# S7CAS-PLEIADES-CARTE-MERE_Pxx_FPGA_bank2.net
KiCad netlist of a schematic drawn in Altium Designer
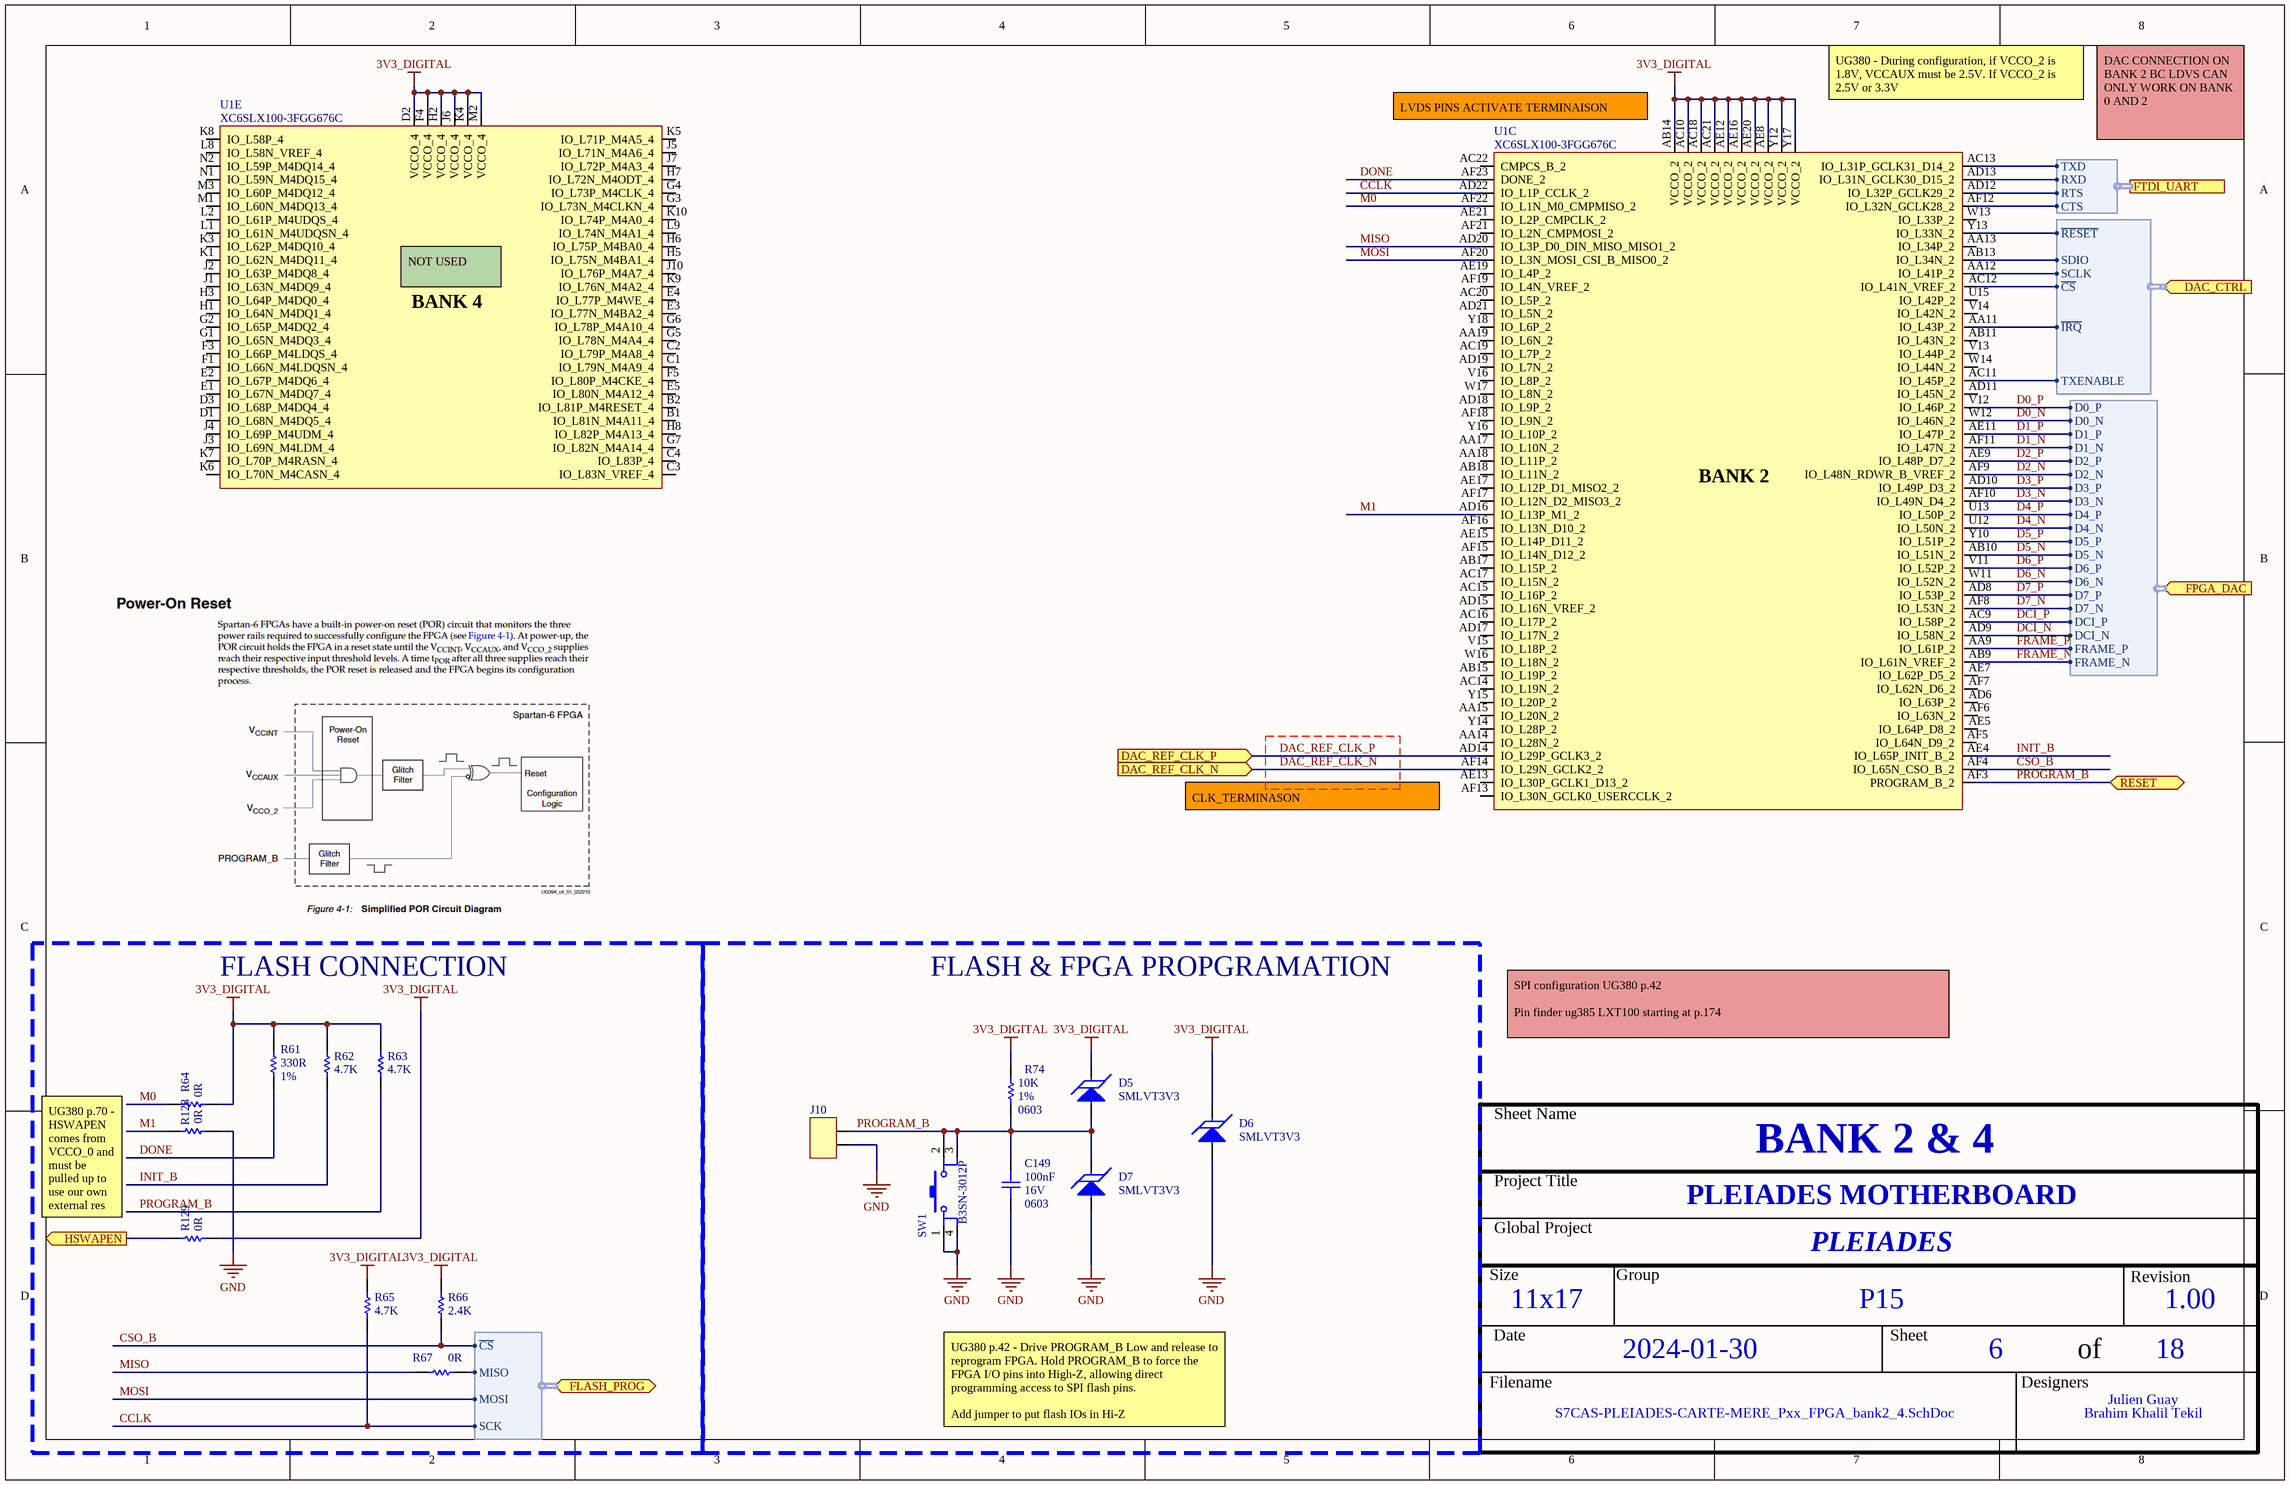
[diagram p0: S7CAS-PLEIADES-CARTE-MERE_Pxx_FPGA_bank2_4.SchDoc]

(export (version "E")
  (design (tool "Eeschema 10.0.6"))
  (components
    (comp (ref "C149")
      (value "100nF")
      (footprint "CAP_0603")
      (description "CAP - 0603")
      (fields
        (field (name "VOLTAGE") "16V")
        (field (name "PACKAGE") "0603")
        (field (name "CREATEDBY") "Jonathan Bouchard")
      )
      (libsource (lib "S7CAS_LIB2023") (part "CAP - 0603"))
    )
    (comp (ref "D5")
      (value "SMLVT3V3")
      (footprint "TVS_POW_SMLVT3V3")
      (description "TVS - 3.3V 10.3V 600W - DO214AA")
      (fields
        (field (name "CREATEDBY/DATE") "Jonathan Bouchard - 2019-04-27")
        (field (name "VERIFIEDBY") "Nicolas V. (2019-05-06)")
      )
      (libsource (lib "S7CAS_LIB2023") (part "TVS_POW_SMLVT3V3"))
    )
    (comp (ref "D6")
      (value "SMLVT3V3")
      (footprint "TVS_POW_SMLVT3V3")
      (description "TVS - 3.3V 10.3V 600W - DO214AA")
      (fields
        (field (name "CREATEDBY/DATE") "Jonathan Bouchard - 2019-04-27")
        (field (name "VERIFIEDBY") "Nicolas V. (2019-05-06)")
      )
      (libsource (lib "S7CAS_LIB2023") (part "TVS_POW_SMLVT3V3"))
    )
    (comp (ref "D7")
      (value "SMLVT3V3")
      (footprint "TVS_POW_SMLVT3V3")
      (description "TVS - 3.3V 10.3V 600W - DO214AA")
      (fields
        (field (name "CREATEDBY/DATE") "Jonathan Bouchard - 2019-04-27")
        (field (name "VERIFIEDBY") "Nicolas V. (2019-05-06)")
      )
      (libsource (lib "S7CAS_LIB2023") (part "TVS_POW_SMLVT3V3"))
    )
    (comp (ref "J10")
      (value "Part Number")
      (footprint "MALE HEADER - 1x2 2.54mm")
      (description "MALE HEADER - 2.54mm 1x2")
      (libsource (lib "S7CAS_LIB2023") (part "MALE HEADER - 1x2 2.54mm"))
    )
    (comp (ref "R61")
      (value "330R")
      (footprint "RES_0603")
      (description "RES - 0603")
      (fields (field (name "PRECISION") "1%") (field (name "CREATEDBY") "Jonathan Bouchard"))
      (libsource (lib "S7CAS_LIB2023") (part "RES - 0603"))
    )
    (comp (ref "R62")
      (value "4.7K")
      (footprint "RES_0603")
      (description "RES - 0603")
      (fields (field (name "CREATEDBY") "Jonathan Bouchard"))
      (libsource (lib "S7CAS_LIB2023") (part "RES - 0603"))
    )
    (comp (ref "R63")
      (value "4.7K")
      (footprint "RES_0603")
      (description "RES - 0603")
      (fields (field (name "CREATEDBY") "Jonathan Bouchard"))
      (libsource (lib "S7CAS_LIB2023") (part "RES - 0603"))
    )
    (comp (ref "R64")
      (value "0R")
      (footprint "RES_0603")
      (description "RES - 0603")
      (fields (field (name "CREATEDBY") "Jonathan Bouchard"))
      (libsource (lib "S7CAS_LIB2023") (part "RES - 0603"))
    )
    (comp (ref "R65")
      (value "4.7K")
      (footprint "RES_0603")
      (description "RES - 0603")
      (fields (field (name "CREATEDBY") "Jonathan Bouchard"))
      (libsource (lib "S7CAS_LIB2023") (part "RES - 0603"))
    )
    (comp (ref "R66")
      (value "2.4K")
      (footprint "RES_0603")
      (description "RES - 0603")
      (fields (field (name "CREATEDBY") "Jonathan Bouchard"))
      (libsource (lib "S7CAS_LIB2023") (part "RES - 0603"))
    )
    (comp (ref "R67")
      (value "0R")
      (footprint "RES_0603")
      (description "RES - 0603")
      (fields (field (name "CREATEDBY") "Jonathan Bouchard"))
      (libsource (lib "S7CAS_LIB2023") (part "RES - 0603"))
    )
    (comp (ref "R74")
      (value "10K")
      (footprint "RES_0603")
      (description "RES - 0603")
      (fields
        (field (name "PACKAGE") "0603")
        (field (name "PRECISION") "1%")
        (field (name "CREATEDBY") "Jonathan Bouchard")
      )
      (libsource (lib "S7CAS_LIB2023") (part "RES - 0603"))
    )
    (comp (ref "R128")
      (value "0R")
      (footprint "RES_0603")
      (description "RES - 0603")
      (fields (field (name "CREATEDBY") "Jonathan Bouchard"))
      (libsource (lib "S7CAS_LIB2023") (part "RES - 0603"))
    )
    (comp (ref "R129")
      (value "0R")
      (footprint "RES_0603")
      (description "RES - 0603")
      (fields (field (name "CREATEDBY") "Jonathan Bouchard"))
      (libsource (lib "S7CAS_LIB2023") (part "RES - 0603"))
    )
    (comp (ref "SW1")
      (value "B3SN-3012P")
      (footprint "SWI_TACT_B3SN-3012P")
      (description "SWI - TACT SPST-NO 0.05A 24V - 4-SMD")
      (fields
        (field (name "MFG") "Omron")
        (field (name "VOLTAGE") "24V")
        (field (name "CREATEDBY") "Jonathan Bouchard")
      )
      (libsource (lib "S7CAS_LIB2023") (part "SWI_TACT_B3SN-3012P"))
    )
    (comp (ref "U1")
      (value "XC6SLX100-3FGG676C")
      (footprint "FPGA_XILINX_FGG676")
      (description "FPGA - XILINX SPARTAN 6 480 I/O - BGA-676")
      (fields
        (field (name "VOLTAGE") "1.14 V ~ 1.26 V")
        (field (name "MFG") "Xilinx")
        (field (name "CREATEDBY") "Jonathan Bouchard")
      )
      (libsource (lib "S7CAS_LIB2023") (part "FPGA_XC6SLX100-3FGG676C"))
    )
  )
  (nets
    (net (code "5") (name "/CCLK") (class "Default")
      (node (ref "R65") (pin "1") (pinfunction "1_1") (pintype "passive"))
      (node (ref "U1") (pin "AD22") (pinfunction "IO_L1P_CCLK_2_AD22") (pintype "passive"))
    )
    (net (code "6") (name "/CSO_B") (class "Default")
      (node (ref "R66") (pin "1") (pinfunction "1_1") (pintype "passive"))
      (node (ref "U1") (pin "AF4") (pinfunction "IO_L65N_CSO_B_2_AF4") (pintype "passive"))
    )
    (net (code "7") (name "/CTS") (class "Default")
      (node (ref "U1") (pin "AF12") (pinfunction "IO_L32N_GCLK28_2_AF12") (pintype "passive"))
    )
    (net (code "8") (name "/D0_N") (class "Default")
      (node (ref "U1") (pin "W12") (pinfunction "IO_L46N_2_W12") (pintype "passive"))
    )
    (net (code "9") (name "/D0_P") (class "Default")
      (node (ref "U1") (pin "V12") (pinfunction "IO_L46P_2_V12") (pintype "passive"))
    )
    (net (code "10") (name "/D1_N") (class "Default")
      (node (ref "U1") (pin "AF11") (pinfunction "IO_L47N_2_AF11") (pintype "passive"))
    )
    (net (code "11") (name "/D1_P") (class "Default")
      (node (ref "U1") (pin "AE11") (pinfunction "IO_L47P_2_AE11") (pintype "passive"))
    )
    (net (code "12") (name "/D2_N") (class "Default")
      (node (ref "U1") (pin "AF9") (pinfunction "IO_L48N_RDWR_B_VREF_2_AF9") (pintype "passive"))
    )
    (net (code "13") (name "/D2_P") (class "Default")
      (node (ref "U1") (pin "AE9") (pinfunction "IO_L48P_D7_2_AE9") (pintype "passive"))
    )
    (net (code "14") (name "/D3_N") (class "Default")
      (node (ref "U1") (pin "AF10") (pinfunction "IO_L49N_D4_2_AF10") (pintype "passive"))
    )
    (net (code "15") (name "/D3_P") (class "Default")
      (node (ref "U1") (pin "AD10") (pinfunction "IO_L49P_D3_2_AD10") (pintype "passive"))
    )
    (net (code "16") (name "/D4_N") (class "Default")
      (node (ref "U1") (pin "U12") (pinfunction "IO_L50N_2_U12") (pintype "passive"))
    )
    (net (code "17") (name "/D4_P") (class "Default")
      (node (ref "U1") (pin "U13") (pinfunction "IO_L50P_2_U13") (pintype "passive"))
    )
    (net (code "18") (name "/D5_N") (class "Default")
      (node (ref "U1") (pin "AB10") (pinfunction "IO_L51N_2_AB10") (pintype "passive"))
    )
    (net (code "19") (name "/D5_P") (class "Default")
      (node (ref "U1") (pin "Y10") (pinfunction "IO_L51P_2_Y10") (pintype "passive"))
    )
    (net (code "20") (name "/D6_N") (class "Default")
      (node (ref "U1") (pin "W11") (pinfunction "IO_L52N_2_W11") (pintype "passive"))
    )
    (net (code "21") (name "/D6_P") (class "Default")
      (node (ref "U1") (pin "V11") (pinfunction "IO_L52P_2_V11") (pintype "passive"))
    )
    (net (code "22") (name "/D7_N") (class "Default")
      (node (ref "U1") (pin "AF8") (pinfunction "IO_L53N_2_AF8") (pintype "passive"))
    )
    (net (code "23") (name "/D7_P") (class "Default")
      (node (ref "U1") (pin "AD8") (pinfunction "IO_L53P_2_AD8") (pintype "passive"))
    )
    (net (code "25") (name "/DAC_REF_CLK_N") (class "Default")
      (node (ref "U1") (pin "AF14") (pinfunction "IO_L29N_GCLK2_2_AF14") (pintype "passive"))
    )
    (net (code "26") (name "/DAC_REF_CLK_P") (class "Default")
      (node (ref "U1") (pin "AD14") (pinfunction "IO_L29P_GCLK3_2_AD14") (pintype "passive"))
    )
    (net (code "27") (name "/DCI_N") (class "Default")
      (node (ref "U1") (pin "AD9") (pinfunction "IO_L58N_2_AD9") (pintype "passive"))
    )
    (net (code "28") (name "/DCI_P") (class "Default")
      (node (ref "U1") (pin "AC9") (pinfunction "IO_L58P_2_AC9") (pintype "passive"))
    )
    (net (code "29") (name "/DONE") (class "Default")
      (node (ref "R61") (pin "1") (pinfunction "1_1") (pintype "passive"))
      (node (ref "U1") (pin "AF23") (pinfunction "DONE_2_AF23") (pintype "passive"))
    )
    (net (code "30") (name "/FRAME_N") (class "Default")
      (node (ref "U1") (pin "AB9") (pinfunction "IO_L61N_VREF_2_AB9") (pintype "passive"))
    )
    (net (code "31") (name "/FRAME_P") (class "Default")
      (node (ref "U1") (pin "AA9") (pinfunction "IO_L61P_2_AA9") (pintype "passive"))
    )
    (net (code "32") (name "/HSWAPEN") (class "Default")
      (node (ref "R129") (pin "1") (pinfunction "1_1") (pintype "passive"))
    )
    (net (code "33") (name "/INIT_B") (class "Default")
      (node (ref "R62") (pin "1") (pinfunction "1_1") (pintype "passive"))
      (node (ref "U1") (pin "AE4") (pinfunction "IO_L65P_INIT_B_2_AE4") (pintype "passive"))
    )
    (net (code "34") (name "/M0") (class "Default")
      (node (ref "R64") (pin "1") (pinfunction "1_1") (pintype "passive"))
      (node (ref "U1") (pin "AF22") (pinfunction "IO_L1N_M0_CMPMISO_2_AF22") (pintype "passive"))
    )
    (net (code "35") (name "/M1") (class "Default")
      (node (ref "R128") (pin "1") (pinfunction "1_1") (pintype "passive"))
      (node (ref "U1") (pin "AD16") (pinfunction "IO_L13P_M1_2_AD16") (pintype "passive"))
    )
    (net (code "36") (name "/MISO") (class "Default")
      (node (ref "R67") (pin "2") (pinfunction "2_2") (pintype "passive"))
      (node (ref "U1") (pin "AD20") (pinfunction "IO_L3P_D0_DIN_MISO_MISO1_2_AD20") (pintype "passive"))
    )
    (net (code "37") (name "/MOSI") (class "Default")
      (node (ref "U1") (pin "AF20") (pinfunction "IO_L3N_MOSI_CSI_B_MISO0_2_AF20") (pintype "passive"))
    )
    (net (code "38") (name "/PROGRAM_B") (class "Default")
      (node (ref "C149") (pin "2") (pinfunction "2_2") (pintype "passive"))
      (node (ref "D5") (pin "A") (pinfunction "A_A") (pintype "passive"))
      (node (ref "D7") (pin "K") (pinfunction "K_K") (pintype "passive"))
      (node (ref "J10") (pin "1") (pinfunction "1_1") (pintype "passive"))
      (node (ref "R63") (pin "1") (pinfunction "1_1") (pintype "passive"))
      (node (ref "R74") (pin "1") (pinfunction "1_1") (pintype "passive"))
      (node (ref "SW1") (pin "2") (pinfunction "2_2") (pintype "passive"))
      (node (ref "SW1") (pin "3") (pinfunction "3_3") (pintype "passive"))
      (node (ref "U1") (pin "AF3") (pinfunction "PROGRAM_B_2_AF3") (pintype "passive"))
    )
    (net (code "39") (name "/RTS") (class "Default")
      (node (ref "U1") (pin "AD12") (pinfunction "IO_L32P_GCLK29_2_AD12") (pintype "passive"))
    )
    (net (code "40") (name "/RXD") (class "Default")
      (node (ref "U1") (pin "AD13") (pinfunction "IO_L31N_GCLK30_D15_2_AD13") (pintype "passive"))
    )
    (net (code "41") (name "/SCLK") (class "Default")
      (node (ref "U1") (pin "AA12") (pinfunction "IO_L41P_2_AA12") (pintype "passive"))
    )
    (net (code "42") (name "/SDIO") (class "Default")
      (node (ref "U1") (pin "AB13") (pinfunction "IO_L34N_2_AB13") (pintype "passive"))
    )
    (net (code "43") (name "/TXD") (class "Default")
      (node (ref "U1") (pin "AC13") (pinfunction "IO_L31P_GCLK31_D14_2_AC13") (pintype "passive"))
    )
    (net (code "44") (name "/TXENABLE") (class "Default")
      (node (ref "U1") (pin "AC11") (pinfunction "IO_L45P_2_AC11") (pintype "passive"))
    )
    (net (code "48") (name "/~{IRQ}") (class "Default")
      (node (ref "U1") (pin "AA11") (pinfunction "IO_L43P_2_AA11") (pintype "passive"))
    )
    (net (code "49") (name "/~{RESET}") (class "Default")
      (node (ref "U1") (pin "Y13") (pinfunction "IO_L33N_2_Y13") (pintype "passive"))
    )
    (net (code "50") (name "3V3_DIGITAL") (class "Default")
      (node (ref "D5") (pin "K") (pinfunction "K_K") (pintype "passive"))
      (node (ref "D6") (pin "K") (pinfunction "K_K") (pintype "passive"))
      (node (ref "R129") (pin "2") (pinfunction "2_2") (pintype "passive"))
      (node (ref "R61") (pin "2") (pinfunction "2_2") (pintype "passive"))
      (node (ref "R62") (pin "2") (pinfunction "2_2") (pintype "passive"))
      (node (ref "R63") (pin "2") (pinfunction "2_2") (pintype "passive"))
      (node (ref "R64") (pin "2") (pinfunction "2_2") (pintype "passive"))
      (node (ref "R65") (pin "2") (pinfunction "2_2") (pintype "passive"))
      (node (ref "R66") (pin "2") (pinfunction "2_2") (pintype "passive"))
      (node (ref "R74") (pin "2") (pinfunction "2_2") (pintype "passive"))
      (node (ref "U1") (pin "AB14") (pinfunction "VCCO_2_AB14") (pintype "passive"))
      (node (ref "U1") (pin "AC10") (pinfunction "VCCO_2_AC10") (pintype "passive"))
      (node (ref "U1") (pin "AC18") (pinfunction "VCCO_2_AC18") (pintype "passive"))
      (node (ref "U1") (pin "AC21") (pinfunction "VCCO_2_AC21") (pintype "passive"))
      (node (ref "U1") (pin "AE12") (pinfunction "VCCO_2_AE12") (pintype "passive"))
      (node (ref "U1") (pin "AE16") (pinfunction "VCCO_2_AE16") (pintype "passive"))
      (node (ref "U1") (pin "AE20") (pinfunction "VCCO_2_AE20") (pintype "passive"))
      (node (ref "U1") (pin "AE8") (pinfunction "VCCO_2_AE8") (pintype "passive"))
      (node (ref "U1") (pin "D2") (pinfunction "VCCO_4_D2") (pintype "passive"))
      (node (ref "U1") (pin "F4") (pinfunction "VCCO_4_F4") (pintype "passive"))
      (node (ref "U1") (pin "H2") (pinfunction "VCCO_4_H2") (pintype "passive"))
      (node (ref "U1") (pin "J6") (pinfunction "VCCO_4_J6") (pintype "passive"))
      (node (ref "U1") (pin "K4") (pinfunction "VCCO_4_K4") (pintype "passive"))
      (node (ref "U1") (pin "M2") (pinfunction "VCCO_4_M2") (pintype "passive"))
      (node (ref "U1") (pin "Y12") (pinfunction "VCCO_2_Y12") (pintype "passive"))
      (node (ref "U1") (pin "Y17") (pinfunction "VCCO_2_Y17") (pintype "passive"))
    )
    (net (code "51") (name "GND") (class "Default")
      (node (ref "C149") (pin "1") (pinfunction "1_1") (pintype "passive"))
      (node (ref "D6") (pin "A") (pinfunction "A_A") (pintype "passive"))
      (node (ref "D7") (pin "A") (pinfunction "A_A") (pintype "passive"))
      (node (ref "J10") (pin "2") (pinfunction "2_2") (pintype "passive"))
      (node (ref "R128") (pin "2") (pinfunction "2_2") (pintype "passive"))
      (node (ref "SW1") (pin "1") (pinfunction "1_1") (pintype "passive"))
      (node (ref "SW1") (pin "4") (pinfunction "4_4") (pintype "passive"))
    )
    (net (code "52") (name "unconnected-(R67-Pad1)") (class "Default")
      (node (ref "R67") (pin "1") (pinfunction "1_1") (pintype "passive"))
    )
    (net (code "53") (name "unconnected-(U1C-CMPCS_B_2-PadAC22)") (class "Default")
      (node (ref "U1") (pin "AC22") (pinfunction "CMPCS_B_2_AC22") (pintype "passive"))
    )
    (net (code "54") (name "unconnected-(U1C-IO_L2N_CMPMOSI_2-PadAF21)") (class "Default")
      (node (ref "U1") (pin "AF21") (pinfunction "IO_L2N_CMPMOSI_2_AF21") (pintype "passive"))
    )
    (net (code "55") (name "unconnected-(U1C-IO_L2P_CMPCLK_2-PadAE21)") (class "Default")
      (node (ref "U1") (pin "AE21") (pinfunction "IO_L2P_CMPCLK_2_AE21") (pintype "passive"))
    )
    (net (code "56") (name "unconnected-(U1C-IO_L4N_VREF_2-PadAF19)") (class "Default")
      (node (ref "U1") (pin "AF19") (pinfunction "IO_L4N_VREF_2_AF19") (pintype "passive"))
    )
    (net (code "57") (name "unconnected-(U1C-IO_L4P_2-PadAE19)") (class "Default")
      (node (ref "U1") (pin "AE19") (pinfunction "IO_L4P_2_AE19") (pintype "passive"))
    )
    (net (code "58") (name "unconnected-(U1C-IO_L5N_2-PadAD21)") (class "Default")
      (node (ref "U1") (pin "AD21") (pinfunction "IO_L5N_2_AD21") (pintype "passive"))
    )
    (net (code "59") (name "unconnected-(U1C-IO_L5P_2-PadAC20)") (class "Default")
      (node (ref "U1") (pin "AC20") (pinfunction "IO_L5P_2_AC20") (pintype "passive"))
    )
    (net (code "60") (name "unconnected-(U1C-IO_L6N_2-PadAA19)") (class "Default")
      (node (ref "U1") (pin "AA19") (pinfunction "IO_L6N_2_AA19") (pintype "passive"))
    )
    (net (code "61") (name "unconnected-(U1C-IO_L6P_2-PadY18)") (class "Default")
      (node (ref "U1") (pin "Y18") (pinfunction "IO_L6P_2_Y18") (pintype "passive"))
    )
    (net (code "62") (name "unconnected-(U1C-IO_L7N_2-PadAD19)") (class "Default")
      (node (ref "U1") (pin "AD19") (pinfunction "IO_L7N_2_AD19") (pintype "passive"))
    )
    (net (code "63") (name "unconnected-(U1C-IO_L7P_2-PadAC19)") (class "Default")
      (node (ref "U1") (pin "AC19") (pinfunction "IO_L7P_2_AC19") (pintype "passive"))
    )
    (net (code "64") (name "unconnected-(U1C-IO_L8N_2-PadW17)") (class "Default")
      (node (ref "U1") (pin "W17") (pinfunction "IO_L8N_2_W17") (pintype "passive"))
    )
    (net (code "65") (name "unconnected-(U1C-IO_L8P_2-PadV16)") (class "Default")
      (node (ref "U1") (pin "V16") (pinfunction "IO_L8P_2_V16") (pintype "passive"))
    )
    (net (code "66") (name "unconnected-(U1C-IO_L9N_2-PadAF18)") (class "Default")
      (node (ref "U1") (pin "AF18") (pinfunction "IO_L9N_2_AF18") (pintype "passive"))
    )
    (net (code "67") (name "unconnected-(U1C-IO_L9P_2-PadAD18)") (class "Default")
      (node (ref "U1") (pin "AD18") (pinfunction "IO_L9P_2_AD18") (pintype "passive"))
    )
    (net (code "68") (name "unconnected-(U1C-IO_L10N_2-PadAA17)") (class "Default")
      (node (ref "U1") (pin "AA17") (pinfunction "IO_L10N_2_AA17") (pintype "passive"))
    )
    (net (code "69") (name "unconnected-(U1C-IO_L10P_2-PadY16)") (class "Default")
      (node (ref "U1") (pin "Y16") (pinfunction "IO_L10P_2_Y16") (pintype "passive"))
    )
    (net (code "70") (name "unconnected-(U1C-IO_L11N_2-PadAB18)") (class "Default")
      (node (ref "U1") (pin "AB18") (pinfunction "IO_L11N_2_AB18") (pintype "passive"))
    )
    (net (code "71") (name "unconnected-(U1C-IO_L11P_2-PadAA18)") (class "Default")
      (node (ref "U1") (pin "AA18") (pinfunction "IO_L11P_2_AA18") (pintype "passive"))
    )
    (net (code "72") (name "unconnected-(U1C-IO_L12N_D2_MISO3_2-PadAF17)") (class "Default")
      (node (ref "U1") (pin "AF17") (pinfunction "IO_L12N_D2_MISO3_2_AF17") (pintype "passive"))
    )
    (net (code "73") (name "unconnected-(U1C-IO_L12P_D1_MISO2_2-PadAE17)") (class "Default")
      (node (ref "U1") (pin "AE17") (pinfunction "IO_L12P_D1_MISO2_2_AE17") (pintype "passive"))
    )
    (net (code "74") (name "unconnected-(U1C-IO_L13N_D10_2-PadAF16)") (class "Default")
      (node (ref "U1") (pin "AF16") (pinfunction "IO_L13N_D10_2_AF16") (pintype "passive"))
    )
    (net (code "75") (name "unconnected-(U1C-IO_L14N_D12_2-PadAF15)") (class "Default")
      (node (ref "U1") (pin "AF15") (pinfunction "IO_L14N_D12_2_AF15") (pintype "passive"))
    )
    (net (code "76") (name "unconnected-(U1C-IO_L14P_D11_2-PadAE15)") (class "Default")
      (node (ref "U1") (pin "AE15") (pinfunction "IO_L14P_D11_2_AE15") (pintype "passive"))
    )
    (net (code "77") (name "unconnected-(U1C-IO_L15N_2-PadAC17)") (class "Default")
      (node (ref "U1") (pin "AC17") (pinfunction "IO_L15N_2_AC17") (pintype "passive"))
    )
    (net (code "78") (name "unconnected-(U1C-IO_L15P_2-PadAB17)") (class "Default")
      (node (ref "U1") (pin "AB17") (pinfunction "IO_L15P_2_AB17") (pintype "passive"))
    )
    (net (code "79") (name "unconnected-(U1C-IO_L16N_VREF_2-PadAD15)") (class "Default")
      (node (ref "U1") (pin "AD15") (pinfunction "IO_L16N_VREF_2_AD15") (pintype "passive"))
    )
    (net (code "80") (name "unconnected-(U1C-IO_L16P_2-PadAC15)") (class "Default")
      (node (ref "U1") (pin "AC15") (pinfunction "IO_L16P_2_AC15") (pintype "passive"))
    )
    (net (code "81") (name "unconnected-(U1C-IO_L17N_2-PadAD17)") (class "Default")
      (node (ref "U1") (pin "AD17") (pinfunction "IO_L17N_2_AD17") (pintype "passive"))
    )
    (net (code "82") (name "unconnected-(U1C-IO_L17P_2-PadAC16)") (class "Default")
      (node (ref "U1") (pin "AC16") (pinfunction "IO_L17P_2_AC16") (pintype "passive"))
    )
    (net (code "83") (name "unconnected-(U1C-IO_L18N_2-PadW16)") (class "Default")
      (node (ref "U1") (pin "W16") (pinfunction "IO_L18N_2_W16") (pintype "passive"))
    )
    (net (code "84") (name "unconnected-(U1C-IO_L18P_2-PadV15)") (class "Default")
      (node (ref "U1") (pin "V15") (pinfunction "IO_L18P_2_V15") (pintype "passive"))
    )
    (net (code "85") (name "unconnected-(U1C-IO_L19N_2-PadAC14)") (class "Default")
      (node (ref "U1") (pin "AC14") (pinfunction "IO_L19N_2_AC14") (pintype "passive"))
    )
    (net (code "86") (name "unconnected-(U1C-IO_L19P_2-PadAB15)") (class "Default")
      (node (ref "U1") (pin "AB15") (pinfunction "IO_L19P_2_AB15") (pintype "passive"))
    )
    (net (code "87") (name "unconnected-(U1C-IO_L20N_2-PadAA15)") (class "Default")
      (node (ref "U1") (pin "AA15") (pinfunction "IO_L20N_2_AA15") (pintype "passive"))
    )
    (net (code "88") (name "unconnected-(U1C-IO_L20P_2-PadY15)") (class "Default")
      (node (ref "U1") (pin "Y15") (pinfunction "IO_L20P_2_Y15") (pintype "passive"))
    )
    (net (code "89") (name "unconnected-(U1C-IO_L28N_2-PadAA14)") (class "Default")
      (node (ref "U1") (pin "AA14") (pinfunction "IO_L28N_2_AA14") (pintype "passive"))
    )
    (net (code "90") (name "unconnected-(U1C-IO_L28P_2-PadY14)") (class "Default")
      (node (ref "U1") (pin "Y14") (pinfunction "IO_L28P_2_Y14") (pintype "passive"))
    )
    (net (code "91") (name "unconnected-(U1C-IO_L30N_GCLK0_USERCCLK_2-PadAF13)") (class "Default")
      (node (ref "U1") (pin "AF13") (pinfunction "IO_L30N_GCLK0_USERCCLK_2_AF13") (pintype "passive"))
    )
    (net (code "92") (name "unconnected-(U1C-IO_L30P_GCLK1_D13_2-PadAE13)") (class "Default")
      (node (ref "U1") (pin "AE13") (pinfunction "IO_L30P_GCLK1_D13_2_AE13") (pintype "passive"))
    )
    (net (code "93") (name "unconnected-(U1C-IO_L33P_2-PadW13)") (class "Default")
      (node (ref "U1") (pin "W13") (pinfunction "IO_L33P_2_W13") (pintype "passive"))
    )
    (net (code "94") (name "unconnected-(U1C-IO_L34P_2-PadAA13)") (class "Default")
      (node (ref "U1") (pin "AA13") (pinfunction "IO_L34P_2_AA13") (pintype "passive"))
    )
    (net (code "95") (name "unconnected-(U1C-IO_L41N_VREF_2-PadAC12)") (class "Default")
      (node (ref "U1") (pin "AC12") (pinfunction "IO_L41N_VREF_2_AC12") (pintype "passive"))
    )
    (net (code "96") (name "unconnected-(U1C-IO_L42N_2-PadV14)") (class "Default")
      (node (ref "U1") (pin "V14") (pinfunction "IO_L42N_2_V14") (pintype "passive"))
    )
    (net (code "97") (name "unconnected-(U1C-IO_L42P_2-PadU15)") (class "Default")
      (node (ref "U1") (pin "U15") (pinfunction "IO_L42P_2_U15") (pintype "passive"))
    )
    (net (code "98") (name "unconnected-(U1C-IO_L43N_2-PadAB11)") (class "Default")
      (node (ref "U1") (pin "AB11") (pinfunction "IO_L43N_2_AB11") (pintype "passive"))
    )
    (net (code "99") (name "unconnected-(U1C-IO_L44N_2-PadW14)") (class "Default")
      (node (ref "U1") (pin "W14") (pinfunction "IO_L44N_2_W14") (pintype "passive"))
    )
    (net (code "100") (name "unconnected-(U1C-IO_L44P_2-PadV13)") (class "Default")
      (node (ref "U1") (pin "V13") (pinfunction "IO_L44P_2_V13") (pintype "passive"))
    )
    (net (code "101") (name "unconnected-(U1C-IO_L45N_2-PadAD11)") (class "Default")
      (node (ref "U1") (pin "AD11") (pinfunction "IO_L45N_2_AD11") (pintype "passive"))
    )
    (net (code "102") (name "unconnected-(U1C-IO_L62N_D6_2-PadAF7)") (class "Default")
      (node (ref "U1") (pin "AF7") (pinfunction "IO_L62N_D6_2_AF7") (pintype "passive"))
    )
    (net (code "103") (name "unconnected-(U1C-IO_L62P_D5_2-PadAE7)") (class "Default")
      (node (ref "U1") (pin "AE7") (pinfunction "IO_L62P_D5_2_AE7") (pintype "passive"))
    )
    (net (code "104") (name "unconnected-(U1C-IO_L63N_2-PadAF6)") (class "Default")
      (node (ref "U1") (pin "AF6") (pinfunction "IO_L63N_2_AF6") (pintype "passive"))
    )
    (net (code "105") (name "unconnected-(U1C-IO_L63P_2-PadAD6)") (class "Default")
      (node (ref "U1") (pin "AD6") (pinfunction "IO_L63P_2_AD6") (pintype "passive"))
    )
    (net (code "106") (name "unconnected-(U1C-IO_L64N_D9_2-PadAF5)") (class "Default")
      (node (ref "U1") (pin "AF5") (pinfunction "IO_L64N_D9_2_AF5") (pintype "passive"))
    )
    (net (code "107") (name "unconnected-(U1C-IO_L64P_D8_2-PadAE5)") (class "Default")
      (node (ref "U1") (pin "AE5") (pinfunction "IO_L64P_D8_2_AE5") (pintype "passive"))
    )
    (net (code "108") (name "unconnected-(U1E-IO_L58N_VREF_4-PadL8)") (class "Default")
      (node (ref "U1") (pin "L8") (pinfunction "IO_L58N_VREF_4_L8") (pintype "passive"))
    )
    (net (code "109") (name "unconnected-(U1E-IO_L58P_4-PadK8)") (class "Default")
      (node (ref "U1") (pin "K8") (pinfunction "IO_L58P_4_K8") (pintype "passive"))
    )
    (net (code "110") (name "unconnected-(U1E-IO_L59N_M4DQ15_4-PadN1)") (class "Default")
      (node (ref "U1") (pin "N1") (pinfunction "IO_L59N_M4DQ15_4_N1") (pintype "passive"))
    )
    (net (code "111") (name "unconnected-(U1E-IO_L59P_M4DQ14_4-PadN2)") (class "Default")
      (node (ref "U1") (pin "N2") (pinfunction "IO_L59P_M4DQ14_4_N2") (pintype "passive"))
    )
    (net (code "112") (name "unconnected-(U1E-IO_L60N_M4DQ13_4-PadM1)") (class "Default")
      (node (ref "U1") (pin "M1") (pinfunction "IO_L60N_M4DQ13_4_M1") (pintype "passive"))
    )
    (net (code "113") (name "unconnected-(U1E-IO_L60P_M4DQ12_4-PadM3)") (class "Default")
      (node (ref "U1") (pin "M3") (pinfunction "IO_L60P_M4DQ12_4_M3") (pintype "passive"))
    )
    (net (code "114") (name "unconnected-(U1E-IO_L61N_M4UDQSN_4-PadL1)") (class "Default")
      (node (ref "U1") (pin "L1") (pinfunction "IO_L61N_M4UDQSN_4_L1") (pintype "passive"))
    )
    (net (code "115") (name "unconnected-(U1E-IO_L61P_M4UDQS_4-PadL2)") (class "Default")
      (node (ref "U1") (pin "L2") (pinfunction "IO_L61P_M4UDQS_4_L2") (pintype "passive"))
    )
    (net (code "116") (name "unconnected-(U1E-IO_L62N_M4DQ11_4-PadK1)") (class "Default")
      (node (ref "U1") (pin "K1") (pinfunction "IO_L62N_M4DQ11_4_K1") (pintype "passive"))
    )
    (net (code "117") (name "unconnected-(U1E-IO_L62P_M4DQ10_4-PadK3)") (class "Default")
      (node (ref "U1") (pin "K3") (pinfunction "IO_L62P_M4DQ10_4_K3") (pintype "passive"))
    )
    (net (code "118") (name "unconnected-(U1E-IO_L63N_M4DQ9_4-PadJ1)") (class "Default")
      (node (ref "U1") (pin "J1") (pinfunction "IO_L63N_M4DQ9_4_J1") (pintype "passive"))
    )
    (net (code "119") (name "unconnected-(U1E-IO_L63P_M4DQ8_4-PadJ2)") (class "Default")
      (node (ref "U1") (pin "J2") (pinfunction "IO_L63P_M4DQ8_4_J2") (pintype "passive"))
    )
    (net (code "120") (name "unconnected-(U1E-IO_L64N_M4DQ1_4-PadH1)") (class "Default")
      (node (ref "U1") (pin "H1") (pinfunction "IO_L64N_M4DQ1_4_H1") (pintype "passive"))
    )
    (net (code "121") (name "unconnected-(U1E-IO_L64P_M4DQ0_4-PadH3)") (class "Default")
      (node (ref "U1") (pin "H3") (pinfunction "IO_L64P_M4DQ0_4_H3") (pintype "passive"))
    )
    (net (code "122") (name "unconnected-(U1E-IO_L65N_M4DQ3_4-PadG1)") (class "Default")
      (node (ref "U1") (pin "G1") (pinfunction "IO_L65N_M4DQ3_4_G1") (pintype "passive"))
    )
    (net (code "123") (name "unconnected-(U1E-IO_L65P_M4DQ2_4-PadG2)") (class "Default")
      (node (ref "U1") (pin "G2") (pinfunction "IO_L65P_M4DQ2_4_G2") (pintype "passive"))
    )
    (net (code "124") (name "unconnected-(U1E-IO_L66N_M4LDQSN_4-PadF1)") (class "Default")
      (node (ref "U1") (pin "F1") (pinfunction "IO_L66N_M4LDQSN_4_F1") (pintype "passive"))
    )
    (net (code "125") (name "unconnected-(U1E-IO_L66P_M4LDQS_4-PadF3)") (class "Default")
      (node (ref "U1") (pin "F3") (pinfunction "IO_L66P_M4LDQS_4_F3") (pintype "passive"))
    )
    (net (code "126") (name "unconnected-(U1E-IO_L67N_M4DQ7_4-PadE1)") (class "Default")
      (node (ref "U1") (pin "E1") (pinfunction "IO_L67N_M4DQ7_4_E1") (pintype "passive"))
    )
    (net (code "127") (name "unconnected-(U1E-IO_L67P_M4DQ6_4-PadE2)") (class "Default")
      (node (ref "U1") (pin "E2") (pinfunction "IO_L67P_M4DQ6_4_E2") (pintype "passive"))
    )
    (net (code "128") (name "unconnected-(U1E-IO_L68N_M4DQ5_4-PadD1)") (class "Default")
      (node (ref "U1") (pin "D1") (pinfunction "IO_L68N_M4DQ5_4_D1") (pintype "passive"))
    )
    (net (code "129") (name "unconnected-(U1E-IO_L68P_M4DQ4_4-PadD3)") (class "Default")
      (node (ref "U1") (pin "D3") (pinfunction "IO_L68P_M4DQ4_4_D3") (pintype "passive"))
    )
    (net (code "130") (name "unconnected-(U1E-IO_L69N_M4LDM_4-PadJ3)") (class "Default")
      (node (ref "U1") (pin "J3") (pinfunction "IO_L69N_M4LDM_4_J3") (pintype "passive"))
    )
    (net (code "131") (name "unconnected-(U1E-IO_L69P_M4UDM_4-PadJ4)") (class "Default")
      (node (ref "U1") (pin "J4") (pinfunction "IO_L69P_M4UDM_4_J4") (pintype "passive"))
    )
    (net (code "132") (name "unconnected-(U1E-IO_L70N_M4CASN_4-PadK6)") (class "Default")
      (node (ref "U1") (pin "K6") (pinfunction "IO_L70N_M4CASN_4_K6") (pintype "passive"))
    )
    (net (code "133") (name "unconnected-(U1E-IO_L70P_M4RASN_4-PadK7)") (class "Default")
      (node (ref "U1") (pin "K7") (pinfunction "IO_L70P_M4RASN_4_K7") (pintype "passive"))
    )
    (net (code "134") (name "unconnected-(U1E-IO_L71N_M4A6_4-PadJ5)") (class "Default")
      (node (ref "U1") (pin "J5") (pinfunction "IO_L71N_M4A6_4_J5") (pintype "passive"))
    )
    (net (code "135") (name "unconnected-(U1E-IO_L71P_M4A5_4-PadK5)") (class "Default")
      (node (ref "U1") (pin "K5") (pinfunction "IO_L71P_M4A5_4_K5") (pintype "passive"))
    )
    (net (code "136") (name "unconnected-(U1E-IO_L72N_M4ODT_4-PadH7)") (class "Default")
      (node (ref "U1") (pin "H7") (pinfunction "IO_L72N_M4ODT_4_H7") (pintype "passive"))
    )
    (net (code "137") (name "unconnected-(U1E-IO_L72P_M4A3_4-PadJ7)") (class "Default")
      (node (ref "U1") (pin "J7") (pinfunction "IO_L72P_M4A3_4_J7") (pintype "passive"))
    )
    (net (code "138") (name "unconnected-(U1E-IO_L73N_M4CLKN_4-PadG3)") (class "Default")
      (node (ref "U1") (pin "G3") (pinfunction "IO_L73N_M4CLKN_4_G3") (pintype "passive"))
    )
    (net (code "139") (name "unconnected-(U1E-IO_L73P_M4CLK_4-PadG4)") (class "Default")
      (node (ref "U1") (pin "G4") (pinfunction "IO_L73P_M4CLK_4_G4") (pintype "passive"))
    )
    (net (code "140") (name "unconnected-(U1E-IO_L74N_M4A1_4-PadL9)") (class "Default")
      (node (ref "U1") (pin "L9") (pinfunction "IO_L74N_M4A1_4_L9") (pintype "passive"))
    )
    (net (code "141") (name "unconnected-(U1E-IO_L74P_M4A0_4-PadK10)") (class "Default")
      (node (ref "U1") (pin "K10") (pinfunction "IO_L74P_M4A0_4_K10") (pintype "passive"))
    )
    (net (code "142") (name "unconnected-(U1E-IO_L75N_M4BA1_4-PadH5)") (class "Default")
      (node (ref "U1") (pin "H5") (pinfunction "IO_L75N_M4BA1_4_H5") (pintype "passive"))
    )
    (net (code "143") (name "unconnected-(U1E-IO_L75P_M4BA0_4-PadH6)") (class "Default")
      (node (ref "U1") (pin "H6") (pinfunction "IO_L75P_M4BA0_4_H6") (pintype "passive"))
    )
    (net (code "144") (name "unconnected-(U1E-IO_L76N_M4A2_4-PadK9)") (class "Default")
      (node (ref "U1") (pin "K9") (pinfunction "IO_L76N_M4A2_4_K9") (pintype "passive"))
    )
    (net (code "145") (name "unconnected-(U1E-IO_L76P_M4A7_4-PadJ10)") (class "Default")
      (node (ref "U1") (pin "J10") (pinfunction "IO_L76P_M4A7_4_J10") (pintype "passive"))
    )
    (net (code "146") (name "unconnected-(U1E-IO_L77N_M4BA2_4-PadE3)") (class "Default")
      (node (ref "U1") (pin "E3") (pinfunction "IO_L77N_M4BA2_4_E3") (pintype "passive"))
    )
    (net (code "147") (name "unconnected-(U1E-IO_L77P_M4WE_4-PadE4)") (class "Default")
      (node (ref "U1") (pin "E4") (pinfunction "IO_L77P_M4WE_4_E4") (pintype "passive"))
    )
    (net (code "148") (name "unconnected-(U1E-IO_L78N_M4A4_4-PadG5)") (class "Default")
      (node (ref "U1") (pin "G5") (pinfunction "IO_L78N_M4A4_4_G5") (pintype "passive"))
    )
    (net (code "149") (name "unconnected-(U1E-IO_L78P_M4A10_4-PadG6)") (class "Default")
      (node (ref "U1") (pin "G6") (pinfunction "IO_L78P_M4A10_4_G6") (pintype "passive"))
    )
    (net (code "150") (name "unconnected-(U1E-IO_L79N_M4A9_4-PadC1)") (class "Default")
      (node (ref "U1") (pin "C1") (pinfunction "IO_L79N_M4A9_4_C1") (pintype "passive"))
    )
    (net (code "151") (name "unconnected-(U1E-IO_L79P_M4A8_4-PadC2)") (class "Default")
      (node (ref "U1") (pin "C2") (pinfunction "IO_L79P_M4A8_4_C2") (pintype "passive"))
    )
    (net (code "152") (name "unconnected-(U1E-IO_L80N_M4A12_4-PadE5)") (class "Default")
      (node (ref "U1") (pin "E5") (pinfunction "IO_L80N_M4A12_4_E5") (pintype "passive"))
    )
    (net (code "153") (name "unconnected-(U1E-IO_L80P_M4CKE_4-PadF5)") (class "Default")
      (node (ref "U1") (pin "F5") (pinfunction "IO_L80P_M4CKE_4_F5") (pintype "passive"))
    )
    (net (code "154") (name "unconnected-(U1E-IO_L81N_M4A11_4-PadB1)") (class "Default")
      (node (ref "U1") (pin "B1") (pinfunction "IO_L81N_M4A11_4_B1") (pintype "passive"))
    )
    (net (code "155") (name "unconnected-(U1E-IO_L81P_M4RESET_4-PadB2)") (class "Default")
      (node (ref "U1") (pin "B2") (pinfunction "IO_L81P_M4RESET_4_B2") (pintype "passive"))
    )
    (net (code "156") (name "unconnected-(U1E-IO_L82N_M4A14_4-PadG7)") (class "Default")
      (node (ref "U1") (pin "G7") (pinfunction "IO_L82N_M4A14_4_G7") (pintype "passive"))
    )
    (net (code "157") (name "unconnected-(U1E-IO_L82P_M4A13_4-PadH8)") (class "Default")
      (node (ref "U1") (pin "H8") (pinfunction "IO_L82P_M4A13_4_H8") (pintype "passive"))
    )
    (net (code "158") (name "unconnected-(U1E-IO_L83N_VREF_4-PadC3)") (class "Default")
      (node (ref "U1") (pin "C3") (pinfunction "IO_L83N_VREF_4_C3") (pintype "passive"))
    )
    (net (code "159") (name "unconnected-(U1E-IO_L83P_4-PadC4)") (class "Default")
      (node (ref "U1") (pin "C4") (pinfunction "IO_L83P_4_C4") (pintype "passive"))
    )
  )
)
